# Altium_Simulation.net
KiCad netlist of a schematic drawn in Altium Designer
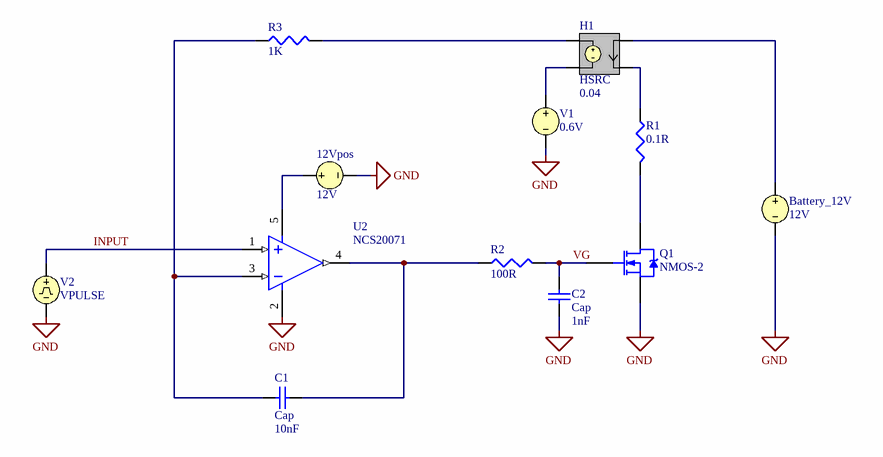
[diagram p0: Altium Simulation.SchDoc]

(export (version "E")
  (design (tool "Eeschema 10.0.6"))
  (components
    (comp (ref "12Vpos")
      (value "12V")
      (description "Voltage Source")
      (fields (field (name "PUBLISHER") "Altium Limited"))
      (libsource (lib "Simulation Sources") (part "VSRC"))
    )
    (comp (ref "Battery_12V")
      (value "12V")
      (description "Voltage Source")
      (fields (field (name "PUBLISHER") "Altium Limited"))
      (libsource (lib "Simulation Sources") (part "VSRC"))
    )
    (comp (ref "C1")
      (value "Cap")
      (footprint "RAD-0.3")
      (description "Capacitor")
      (fields (field (name "ALTIUM_VALUE") "10nF") (field (name "PUBLISHER") "Altium Limited"))
      (libsource (lib "Miscellaneous Devices") (part "Cap"))
    )
    (comp (ref "C2")
      (value "Cap")
      (footprint "RAD-0.3")
      (description "Capacitor")
      (fields (field (name "ALTIUM_VALUE") "1nF") (field (name "PUBLISHER") "Altium Limited"))
      (libsource (lib "Miscellaneous Devices") (part "Cap"))
    )
    (comp (ref "H1")
      (value "HSRC")
      (description "Current Controlled Voltage Source")
      (fields (field (name "GAIN") "0.04") (field (name "PUBLISHER") "Altium Limited"))
      (libsource (lib "Simulation Sources") (part "HSRC"))
    )
    (comp (ref "Q1")
      (value "NMOS-2")
      (footprint "TO-220AB")
      (description "N-Channel Power MOSFET")
      (fields (field (name "PUBLISHER") "Altium Limited"))
      (libsource (lib "Miscellaneous Devices") (part "NMOS-2"))
    )
    (comp (ref "R1")
      (value "0.1R")
      (footprint "J1-0603")
      (description "Resistor")
      (fields (field (name "PUBLISHER") "Altium Limited"))
      (libsource (lib "Miscellaneous Devices") (part "Res3"))
    )
    (comp (ref "R2")
      (value "100R")
      (footprint "J1-0603")
      (description "Resistor")
      (fields (field (name "PUBLISHER") "Altium Limited"))
      (libsource (lib "Miscellaneous Devices") (part "Res3"))
    )
    (comp (ref "R3")
      (value "1K")
      (footprint "J1-0603")
      (description "Resistor")
      (fields (field (name "PUBLISHER") "Altium Limited"))
      (libsource (lib "Miscellaneous Devices") (part "Res3"))
    )
    (comp (ref "U2")
      (value "NCS20071")
      (footprint "SOT-553-5")
      (description "Rail-to-Rail Input/Output, 3 MHz Op Amps")
      (fields
        (field (name "1 SUPPLIER PART NUMBER") "MCP6021-E/SN-ND")
        (field (name "MANUFACTURER") "Microchip Technology")
      )
      (libsource (lib "Library_20-02-20") (part "NCS20071"))
    )
    (comp (ref "V1")
      (value "0.6V")
      (description "Voltage Source")
      (fields (field (name "PUBLISHER") "Altium Limited"))
      (libsource (lib "Simulation Sources") (part "VSRC"))
    )
    (comp (ref "V2")
      (value "VPULSE")
      (description "Pulse Voltage Source")
      (fields (field (name "PUBLISHER") "Altium Limited"))
      (libsource (lib "Simulation Sources") (part "VPULSE"))
    )
  )
  (nets
    (net (code "1") (name "/INPUT") (class "Default")
      (node (ref "U2") (pin "1") (pintype "input"))
      (node (ref "V2") (pin "1") (pinfunction "1_1") (pintype "passive"))
    )
    (net (code "2") (name "/VG") (class "Default")
      (node (ref "C2") (pin "2") (pinfunction "2_2") (pintype "passive"))
      (node (ref "Q1") (pin "1") (pinfunction "G_1") (pintype "passive"))
      (node (ref "R2") (pin "2") (pinfunction "2_2") (pintype "passive"))
    )
    (net (code "3") (name "GND") (class "Default")
      (node (ref "12Vpos") (pin "2") (pinfunction "2_2") (pintype "passive"))
      (node (ref "Battery_12V") (pin "2") (pinfunction "2_2") (pintype "passive"))
      (node (ref "C2") (pin "1") (pinfunction "1_1") (pintype "passive"))
      (node (ref "Q1") (pin "3") (pinfunction "S_3") (pintype "passive"))
      (node (ref "U2") (pin "2") (pintype "power_in"))
      (node (ref "V1") (pin "2") (pinfunction "2_2") (pintype "passive"))
      (node (ref "V2") (pin "2") (pinfunction "2_2") (pintype "passive"))
    )
    (net (code "4") (name "Net-(12Vpos-Pad1)") (class "Default")
      (node (ref "12Vpos") (pin "1") (pinfunction "1_1") (pintype "passive"))
      (node (ref "U2") (pin "5") (pintype "power_in"))
    )
    (net (code "5") (name "Net-(C1-Pad1)") (class "Default")
      (node (ref "C1") (pin "1") (pinfunction "1_1") (pintype "passive"))
      (node (ref "R3") (pin "1") (pinfunction "1_1") (pintype "passive"))
      (node (ref "U2") (pin "3") (pintype "input"))
    )
    (net (code "6") (name "Net-(C1-Pad2)") (class "Default")
      (node (ref "C1") (pin "2") (pinfunction "2_2") (pintype "passive"))
      (node (ref "R2") (pin "1") (pinfunction "1_1") (pintype "passive"))
      (node (ref "U2") (pin "4") (pintype "output"))
    )
    (net (code "7") (name "Net-(H1-N+)") (class "Default")
      (node (ref "H1") (pin "3") (pinfunction "N+_3") (pintype "passive"))
      (node (ref "R3") (pin "2") (pinfunction "2_2") (pintype "passive"))
    )
    (net (code "8") (name "Net-(H1-N-)") (class "Default")
      (node (ref "H1") (pin "4") (pinfunction "N-_4") (pintype "passive"))
      (node (ref "V1") (pin "1") (pinfunction "1_1") (pintype "passive"))
    )
    (net (code "9") (name "Net-(H1-NC+)") (class "Default")
      (node (ref "Battery_12V") (pin "1") (pinfunction "1_1") (pintype "passive"))
      (node (ref "H1") (pin "1") (pinfunction "NC+_1") (pintype "passive"))
    )
    (net (code "10") (name "Net-(H1-NC-)") (class "Default")
      (node (ref "H1") (pin "2") (pinfunction "NC-_2") (pintype "passive"))
      (node (ref "R1") (pin "1") (pinfunction "1_1") (pintype "passive"))
    )
    (net (code "11") (name "Net-(Q1-D)") (class "Default")
      (node (ref "Q1") (pin "2") (pinfunction "D_2") (pintype "passive"))
      (node (ref "R1") (pin "2") (pinfunction "2_2") (pintype "passive"))
    )
  )
)
